# HYDRA_V4_LINK.net
KiCad netlist of a schematic drawn in Altium Designer
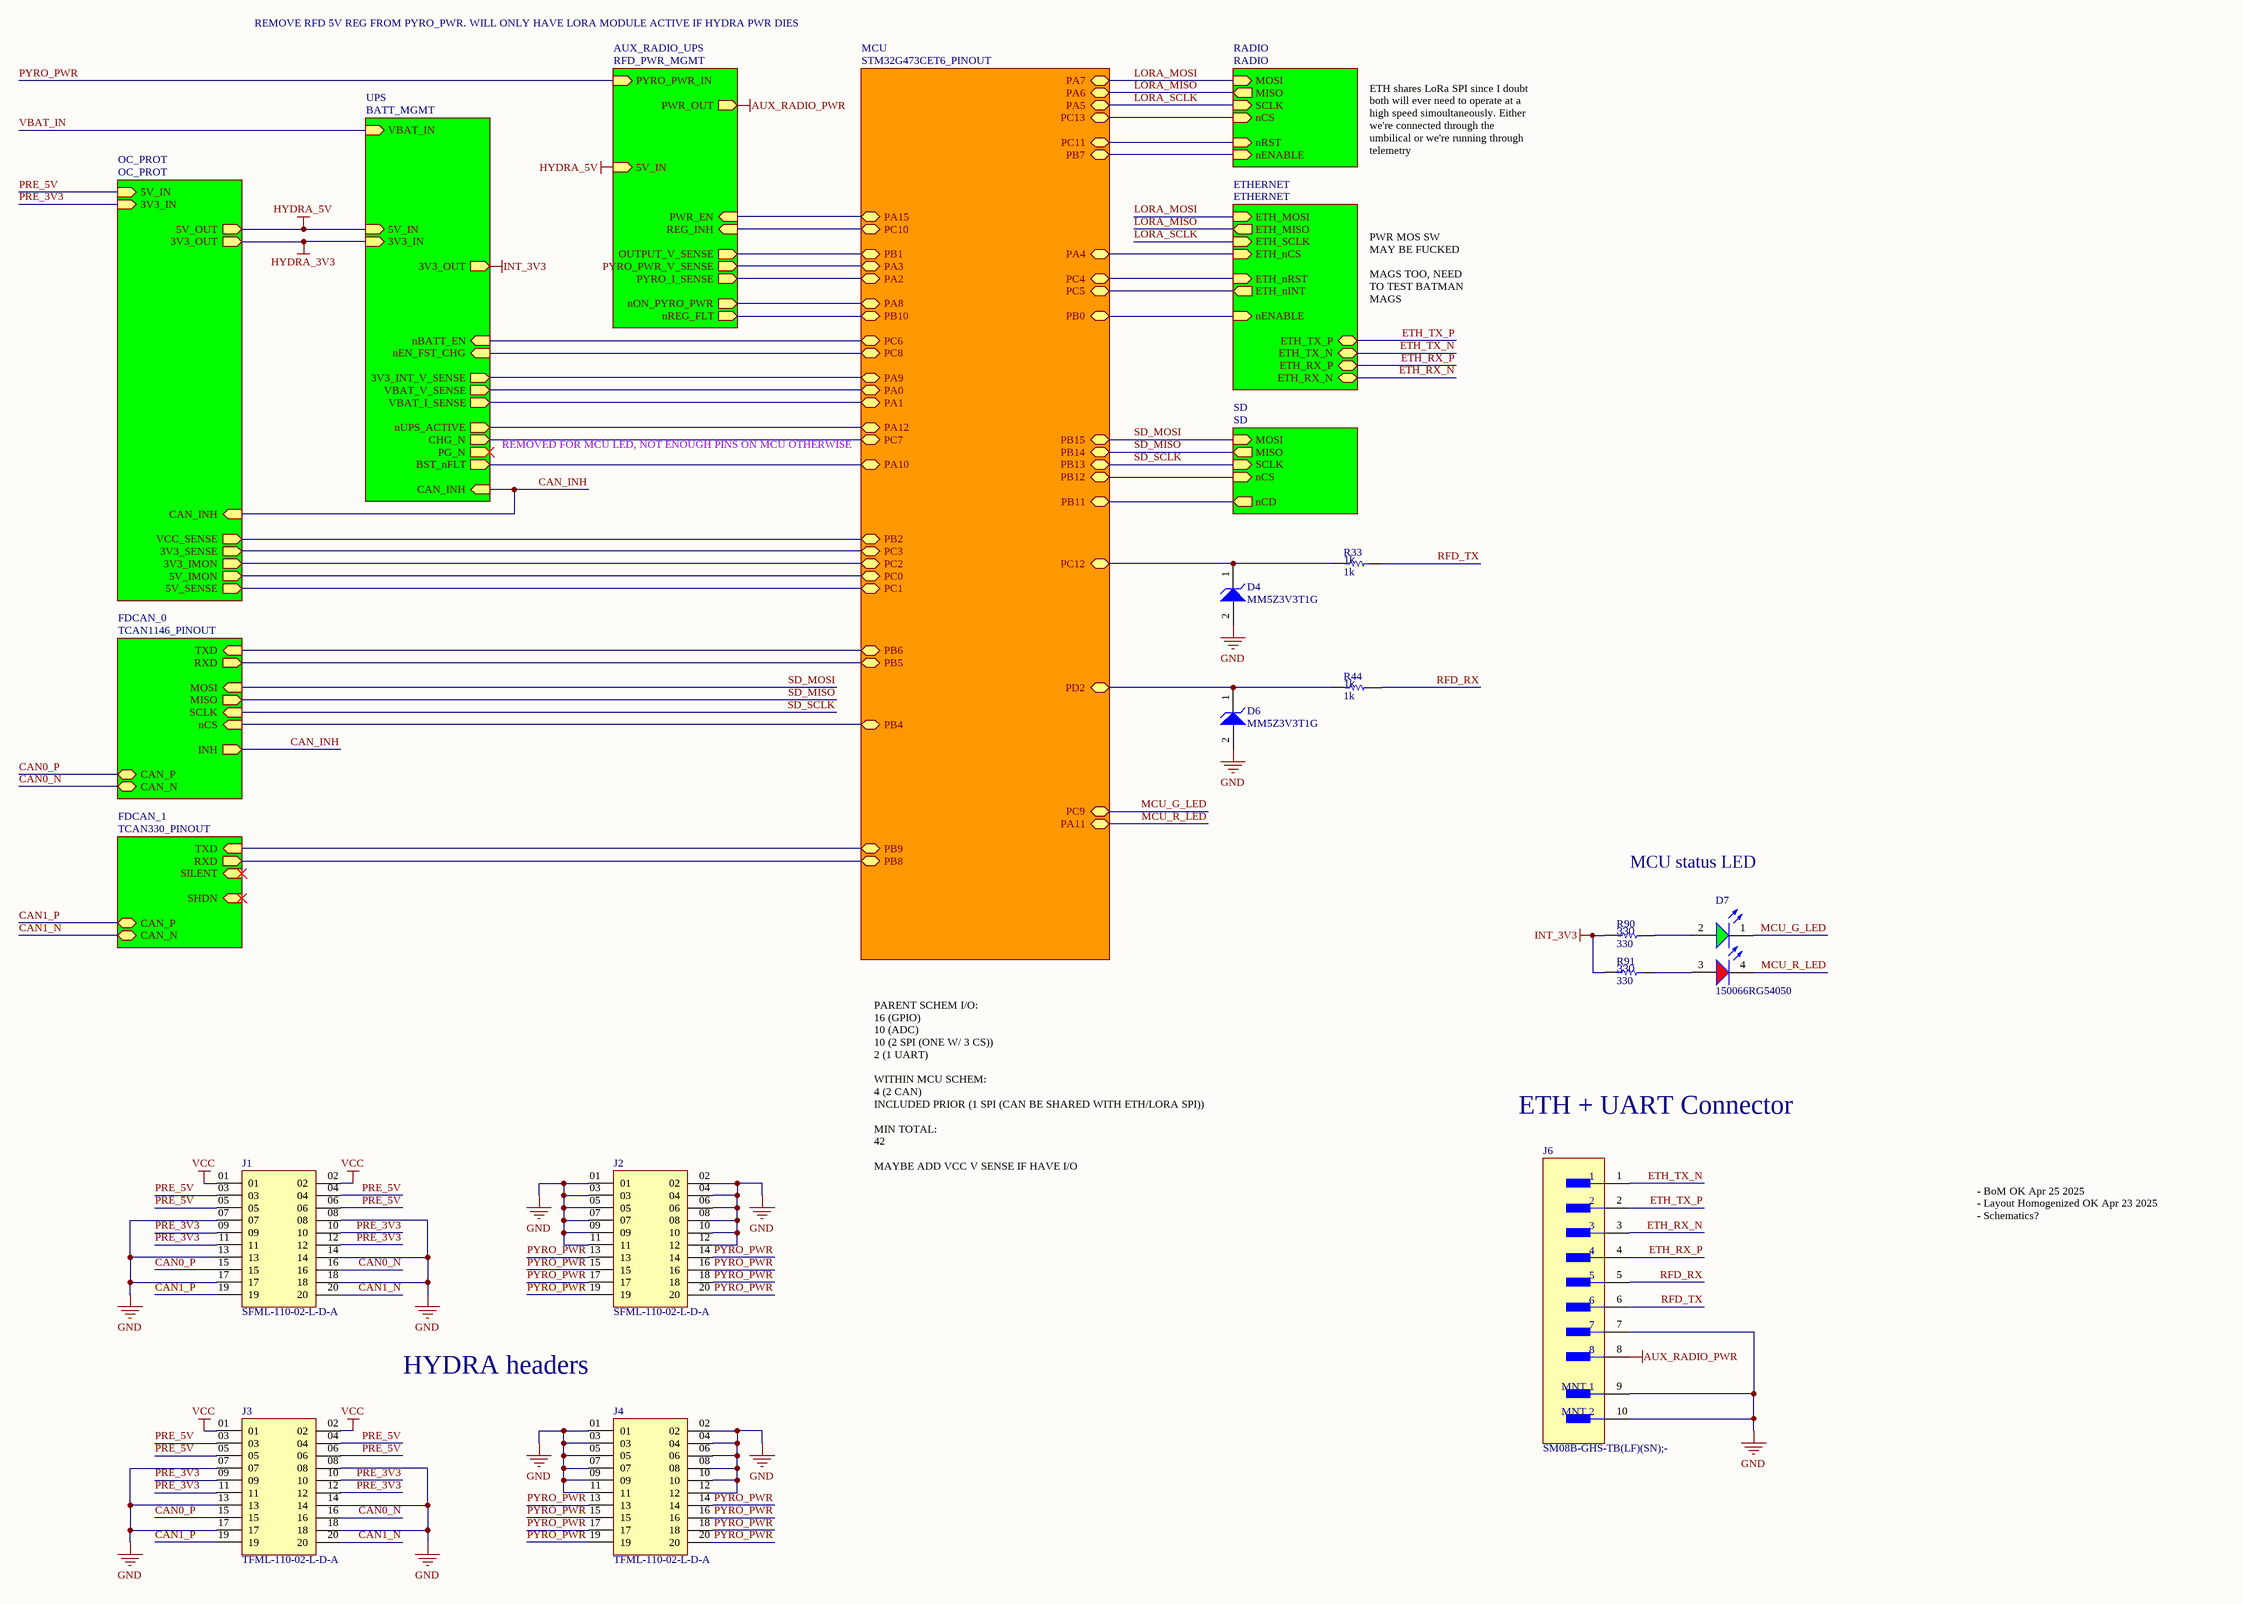
[diagram p0: HYDRA_V4_LINK.SchDoc]

(export (version "E")
  (design (tool "Eeschema 10.0.6"))
  (components
    (comp (ref "D4")
      (value "MM5Z3V3T1G")
      (footprint "ONSC-SOD-523-2-502-01_V")
      (description "Zener Voltage Regulator, 500 mW, 2-Pin SOD-523, Pb-Free, Tape and Reel")
      (fields (field (name "MANUFACTURER") "On Semiconductor"))
      (libsource (lib "Altium Content Vault") (part "ONSC-K1A2-2"))
    )
    (comp (ref "D6")
      (value "MM5Z3V3T1G")
      (footprint "ONSC-SOD-523-2-502-01_V")
      (description "Zener Voltage Regulator, 500 mW, 2-Pin SOD-523, Pb-Free, Tape and Reel")
      (fields (field (name "MANUFACTURER") "On Semiconductor"))
      (libsource (lib "Altium Content Vault") (part "ONSC-K1A2-2"))
    )
    (comp (ref "D7")
      (value "150066RG54050")
      (footprint "WL-SBCD_0606")
      (description "Led, Red/Grn, 180Mcd/230Mcd, 624Nm/525Nm Rohs Compliant: Yes")
      (fields (field (name "SOURCE") "rgled.SchLib"))
      (libsource (lib "Space Concordia") (part "CMP-004-00034-2"))
    )
    (comp (ref "J1")
      (value "SFML-110-02-L-D-A")
      (footprint "SFML-110-02-L-D-A-Footprint-1")
      (libsource (lib "Space Concordia") (part "SFML-110-02-L-D-A"))
    )
    (comp (ref "J2")
      (value "SFML-110-02-L-D-A")
      (footprint "SFML-110-02-L-D-A-Footprint-1")
      (libsource (lib "Space Concordia") (part "SFML-110-02-L-D-A"))
    )
    (comp (ref "J3")
      (value "TFML-110-02-L-D-A")
      (footprint "TFML-110-02-L-D-A-Footprint-1")
      (description "Board Connector, 20 Contact(s), 2 Row(s), Male, Straight, Surface Mount Terminal")
      (libsource (lib "Space Concordia") (part "TFML-110-02-L-D-A"))
    )
    (comp (ref "J4")
      (value "TFML-110-02-L-D-A")
      (footprint "TFML-110-02-L-D-A-Footprint-1")
      (description "Board Connector, 20 Contact(s), 2 Row(s), Male, Straight, Surface Mount Terminal")
      (libsource (lib "Space Concordia") (part "TFML-110-02-L-D-A"))
    )
    (comp (ref "J6")
      (value "SM08B-GHS-TB(LF)(SN);-")
      (footprint "SM08B-GHS-TB(LF)(SN);--Footprint-1")
      (libsource (lib "Space Concordia") (part "SM08B-GHS-TB(LF)(SN)"))
    )
    (comp (ref "R33")
      (value "1k")
      (footprint "R0603B")
      (description "Resistor")
      (fields (field (name "ALTIUM_VALUE") "1k"))
      (libsource (lib "Space Concordia") (part "Resistor"))
    )
    (comp (ref "R44")
      (value "1k")
      (footprint "R0603B")
      (description "Resistor")
      (fields (field (name "ALTIUM_VALUE") "1k"))
      (libsource (lib "Space Concordia") (part "Resistor"))
    )
    (comp (ref "R90")
      (value "330")
      (footprint "R0603B")
      (description "Resistor")
      (fields (field (name "ALTIUM_VALUE") "330"))
      (libsource (lib "Space Concordia") (part "Resistor"))
    )
    (comp (ref "R91")
      (value "330")
      (footprint "R0603B")
      (description "Resistor")
      (fields (field (name "ALTIUM_VALUE") "330"))
      (libsource (lib "Space Concordia") (part "Resistor"))
    )
  )
  (nets
    (net (code "7") (name "/CAN0_N") (class "Default")
      (node (ref "J1") (pin "16") (pinfunction "16_16") (pintype "passive"))
      (node (ref "J3") (pin "16") (pinfunction "16_16") (pintype "passive"))
    )
    (net (code "8") (name "/CAN0_P") (class "Default")
      (node (ref "J1") (pin "15") (pinfunction "15_15") (pintype "passive"))
      (node (ref "J3") (pin "15") (pinfunction "15_15") (pintype "passive"))
    )
    (net (code "9") (name "/CAN1_N") (class "Default")
      (node (ref "J1") (pin "20") (pinfunction "20_20") (pintype "passive"))
      (node (ref "J3") (pin "20") (pinfunction "20_20") (pintype "passive"))
    )
    (net (code "10") (name "/CAN1_P") (class "Default")
      (node (ref "J1") (pin "19") (pinfunction "19_19") (pintype "passive"))
      (node (ref "J3") (pin "19") (pinfunction "19_19") (pintype "passive"))
    )
    (net (code "13") (name "/ETH_RX_N") (class "Default")
      (node (ref "J6") (pin "3") (pinfunction "3_3") (pintype "passive"))
    )
    (net (code "14") (name "/ETH_RX_P") (class "Default")
      (node (ref "J6") (pin "4") (pinfunction "4_4") (pintype "passive"))
    )
    (net (code "15") (name "/ETH_TX_N") (class "Default")
      (node (ref "J6") (pin "1") (pinfunction "1_1") (pintype "passive"))
    )
    (net (code "16") (name "/ETH_TX_P") (class "Default")
      (node (ref "J6") (pin "2") (pinfunction "2_2") (pintype "passive"))
    )
    (net (code "23") (name "/MCU_G_LED") (class "Default")
      (node (ref "D7") (pin "1") (pinfunction "K_1") (pintype "passive"))
    )
    (net (code "24") (name "/MCU_R_LED") (class "Default")
      (node (ref "D7") (pin "4") (pinfunction "K_4") (pintype "passive"))
    )
    (net (code "37") (name "/PC12") (class "Default")
      (node (ref "D4") (pin "1") (pinfunction "K_1") (pintype "passive"))
      (node (ref "R33") (pin "2") (pinfunction "2_2") (pintype "passive"))
    )
    (net (code "39") (name "/PD2") (class "Default")
      (node (ref "D6") (pin "1") (pinfunction "K_1") (pintype "passive"))
      (node (ref "R44") (pin "2") (pinfunction "2_2") (pintype "passive"))
    )
    (net (code "41") (name "/PRE_3V3") (class "Default")
      (node (ref "J1") (pin "09") (pinfunction "09_09") (pintype "passive"))
      (node (ref "J1") (pin "10") (pinfunction "10_10") (pintype "passive"))
      (node (ref "J1") (pin "11") (pinfunction "11_11") (pintype "passive"))
      (node (ref "J1") (pin "12") (pinfunction "12_12") (pintype "passive"))
      (node (ref "J3") (pin "09") (pinfunction "09_09") (pintype "passive"))
      (node (ref "J3") (pin "10") (pinfunction "10_10") (pintype "passive"))
      (node (ref "J3") (pin "11") (pinfunction "11_11") (pintype "passive"))
      (node (ref "J3") (pin "12") (pinfunction "12_12") (pintype "passive"))
    )
    (net (code "42") (name "/PRE_5V") (class "Default")
      (node (ref "J1") (pin "03") (pinfunction "03_03") (pintype "passive"))
      (node (ref "J1") (pin "04") (pinfunction "04_04") (pintype "passive"))
      (node (ref "J1") (pin "05") (pinfunction "05_05") (pintype "passive"))
      (node (ref "J1") (pin "06") (pinfunction "06_06") (pintype "passive"))
      (node (ref "J3") (pin "03") (pinfunction "03_03") (pintype "passive"))
      (node (ref "J3") (pin "04") (pinfunction "04_04") (pintype "passive"))
      (node (ref "J3") (pin "05") (pinfunction "05_05") (pintype "passive"))
      (node (ref "J3") (pin "06") (pinfunction "06_06") (pintype "passive"))
    )
    (net (code "44") (name "/PYRO_PWR") (class "Default")
      (node (ref "J2") (pin "13") (pinfunction "13_13") (pintype "passive"))
      (node (ref "J2") (pin "14") (pinfunction "14_14") (pintype "passive"))
      (node (ref "J2") (pin "15") (pinfunction "15_15") (pintype "passive"))
      (node (ref "J2") (pin "16") (pinfunction "16_16") (pintype "passive"))
      (node (ref "J2") (pin "17") (pinfunction "17_17") (pintype "passive"))
      (node (ref "J2") (pin "18") (pinfunction "18_18") (pintype "passive"))
      (node (ref "J2") (pin "19") (pinfunction "19_19") (pintype "passive"))
      (node (ref "J2") (pin "20") (pinfunction "20_20") (pintype "passive"))
      (node (ref "J4") (pin "13") (pinfunction "13_13") (pintype "passive"))
      (node (ref "J4") (pin "14") (pinfunction "14_14") (pintype "passive"))
      (node (ref "J4") (pin "15") (pinfunction "15_15") (pintype "passive"))
      (node (ref "J4") (pin "16") (pinfunction "16_16") (pintype "passive"))
      (node (ref "J4") (pin "17") (pinfunction "17_17") (pintype "passive"))
      (node (ref "J4") (pin "18") (pinfunction "18_18") (pintype "passive"))
      (node (ref "J4") (pin "19") (pinfunction "19_19") (pintype "passive"))
      (node (ref "J4") (pin "20") (pinfunction "20_20") (pintype "passive"))
    )
    (net (code "46") (name "/RFD_RX") (class "Default")
      (node (ref "J6") (pin "5") (pinfunction "5_5") (pintype "passive"))
      (node (ref "R44") (pin "1") (pinfunction "1_1") (pintype "passive"))
    )
    (net (code "47") (name "/RFD_TX") (class "Default")
      (node (ref "J6") (pin "6") (pinfunction "6_6") (pintype "passive"))
      (node (ref "R33") (pin "1") (pinfunction "1_1") (pintype "passive"))
    )
    (net (code "63") (name "AUX_RADIO_PWR") (class "Default")
      (node (ref "J6") (pin "8") (pinfunction "8_8") (pintype "passive"))
    )
    (net (code "64") (name "GND") (class "Default")
      (node (ref "D4") (pin "2") (pinfunction "A_2") (pintype "passive"))
      (node (ref "D6") (pin "2") (pinfunction "A_2") (pintype "passive"))
      (node (ref "J1") (pin "07") (pinfunction "07_07") (pintype "passive"))
      (node (ref "J1") (pin "08") (pinfunction "08_08") (pintype "passive"))
      (node (ref "J1") (pin "13") (pinfunction "13_13") (pintype "passive"))
      (node (ref "J1") (pin "14") (pinfunction "14_14") (pintype "passive"))
      (node (ref "J1") (pin "17") (pinfunction "17_17") (pintype "passive"))
      (node (ref "J1") (pin "18") (pinfunction "18_18") (pintype "passive"))
      (node (ref "J2") (pin "01") (pinfunction "01_01") (pintype "passive"))
      (node (ref "J2") (pin "02") (pinfunction "02_02") (pintype "passive"))
      (node (ref "J2") (pin "03") (pinfunction "03_03") (pintype "passive"))
      (node (ref "J2") (pin "04") (pinfunction "04_04") (pintype "passive"))
      (node (ref "J2") (pin "05") (pinfunction "05_05") (pintype "passive"))
      (node (ref "J2") (pin "06") (pinfunction "06_06") (pintype "passive"))
      (node (ref "J2") (pin "07") (pinfunction "07_07") (pintype "passive"))
      (node (ref "J2") (pin "08") (pinfunction "08_08") (pintype "passive"))
      (node (ref "J2") (pin "09") (pinfunction "09_09") (pintype "passive"))
      (node (ref "J2") (pin "10") (pinfunction "10_10") (pintype "passive"))
      (node (ref "J2") (pin "11") (pinfunction "11_11") (pintype "passive"))
      (node (ref "J2") (pin "12") (pinfunction "12_12") (pintype "passive"))
      (node (ref "J3") (pin "07") (pinfunction "07_07") (pintype "passive"))
      (node (ref "J3") (pin "08") (pinfunction "08_08") (pintype "passive"))
      (node (ref "J3") (pin "13") (pinfunction "13_13") (pintype "passive"))
      (node (ref "J3") (pin "14") (pinfunction "14_14") (pintype "passive"))
      (node (ref "J3") (pin "17") (pinfunction "17_17") (pintype "passive"))
      (node (ref "J3") (pin "18") (pinfunction "18_18") (pintype "passive"))
      (node (ref "J4") (pin "01") (pinfunction "01_01") (pintype "passive"))
      (node (ref "J4") (pin "02") (pinfunction "02_02") (pintype "passive"))
      (node (ref "J4") (pin "03") (pinfunction "03_03") (pintype "passive"))
      (node (ref "J4") (pin "04") (pinfunction "04_04") (pintype "passive"))
      (node (ref "J4") (pin "05") (pinfunction "05_05") (pintype "passive"))
      (node (ref "J4") (pin "06") (pinfunction "06_06") (pintype "passive"))
      (node (ref "J4") (pin "07") (pinfunction "07_07") (pintype "passive"))
      (node (ref "J4") (pin "08") (pinfunction "08_08") (pintype "passive"))
      (node (ref "J4") (pin "09") (pinfunction "09_09") (pintype "passive"))
      (node (ref "J4") (pin "10") (pinfunction "10_10") (pintype "passive"))
      (node (ref "J4") (pin "11") (pinfunction "11_11") (pintype "passive"))
      (node (ref "J4") (pin "12") (pinfunction "12_12") (pintype "passive"))
      (node (ref "J6") (pin "10") (pinfunction "MNT_2_10") (pintype "passive"))
      (node (ref "J6") (pin "7") (pinfunction "7_7") (pintype "passive"))
      (node (ref "J6") (pin "9") (pinfunction "MNT_1_9") (pintype "passive"))
    )
    (net (code "67") (name "INT_3V3") (class "Default")
      (node (ref "R90") (pin "2") (pinfunction "2_2") (pintype "passive"))
      (node (ref "R91") (pin "2") (pinfunction "2_2") (pintype "passive"))
    )
    (net (code "68") (name "Net-(D7-A-Pad2)") (class "Default")
      (node (ref "D7") (pin "2") (pinfunction "A_2") (pintype "passive"))
      (node (ref "R90") (pin "1") (pinfunction "1_1") (pintype "passive"))
    )
    (net (code "69") (name "Net-(D7-A-Pad3)") (class "Default")
      (node (ref "D7") (pin "3") (pinfunction "A_3") (pintype "passive"))
      (node (ref "R91") (pin "1") (pinfunction "1_1") (pintype "passive"))
    )
    (net (code "70") (name "VCC") (class "Default")
      (node (ref "J1") (pin "01") (pinfunction "01_01") (pintype "passive"))
      (node (ref "J1") (pin "02") (pinfunction "02_02") (pintype "passive"))
      (node (ref "J3") (pin "01") (pinfunction "01_01") (pintype "passive"))
      (node (ref "J3") (pin "02") (pinfunction "02_02") (pintype "passive"))
    )
  )
)
